# d_pubsub_lower_isolate_220V_common.net
KiCad netlist of a schematic drawn in EAGLE
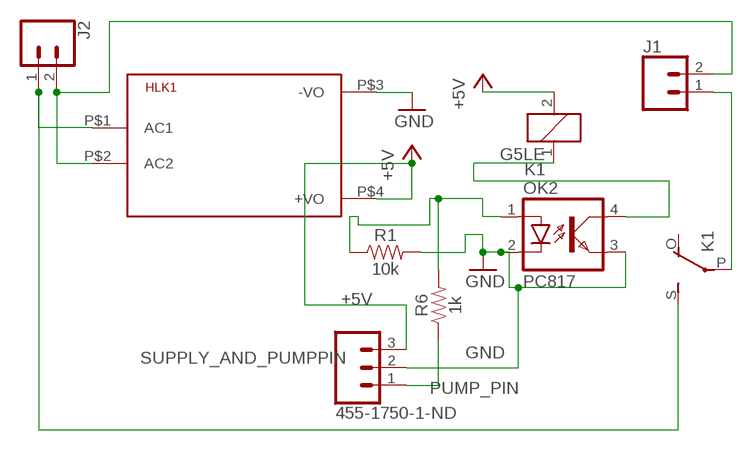
[diagram p0: schematic, sheet 1]

(export (version "E")
  (design (tool "Eeschema 10.0.6"))
  (components
    (comp (ref "HLK1")
      (value "HLK-PM013W")
      (footprint "eagle-import:HLK-PM01")
      (libsource (lib "eagle-import") (part "HLK-PM013W"))
    )
    (comp (ref "J1")
      (value "CONN_025MM")
      (footprint "eagle-import:SCREWTERMINAL-5MM-2")
      (libsource (lib "eagle-import") (part "CONN_025MM"))
    )
    (comp (ref "J2")
      (value "CONN_025MM")
      (footprint "eagle-import:SCREWTERMINAL-5MM-2")
      (libsource (lib "eagle-import") (part "CONN_025MM"))
    )
    (comp (ref "K1")
      (value "G5LE")
      (footprint "eagle-import:G5LE")
      (libsource (lib "eagle-import") (part "G5LE"))
    )
    (comp (ref "OK2")
      (value "PC817")
      (footprint "eagle-import:DIL04")
      (fields (field (name "MPN") "PC817X4J000F"))
      (libsource (lib "eagle-import") (part "PC817"))
    )
    (comp (ref "R1")
      (value "10k")
      (footprint "eagle-import:AXIAL-0.3")
      (libsource (lib "eagle-import") (part "10KOHM-HORIZ-1/4W-1%"))
    )
    (comp (ref "R6")
      (value "1k")
      (footprint "eagle-import:AXIAL-0.3")
      (libsource (lib "eagle-import") (part "1KOHM-HORIZ-1/4W-1%"))
    )
    (comp (ref "SUPPLY_AND_PUMPPIN")
      (value "455-1750-1-ND")
      (footprint "eagle-import:1X03")
      (libsource (lib "eagle-import") (part "CONN_03"))
    )
  )
  (nets
    (net (code "1") (name "+5V") (class "Default")
      (node (ref "HLK1") (pin "P$4") (pinfunction "+VO_P$4") (pintype "bidirectional"))
      (node (ref "K1") (pin "2") (pinfunction "2_2") (pintype "passive"))
      (node (ref "SUPPLY_AND_PUMPPIN") (pin "3") (pinfunction "3_3") (pintype "passive"))
    )
    (net (code "2") (name "/PUMP_PIN") (class "Default")
      (node (ref "R6") (pin "P$1") (pinfunction "1_P$1") (pintype "passive"))
      (node (ref "SUPPLY_AND_PUMPPIN") (pin "1") (pinfunction "1_1") (pintype "passive"))
    )
    (net (code "3") (name "GND") (class "Default")
      (node (ref "HLK1") (pin "P$3") (pinfunction "-VO_P$3") (pintype "bidirectional"))
      (node (ref "OK2") (pin "2") (pinfunction "C_2") (pintype "passive"))
      (node (ref "OK2") (pin "3") (pinfunction "EMIT_3") (pintype "passive"))
      (node (ref "R1") (pin "P$2") (pinfunction "2_P$2") (pintype "passive"))
      (node (ref "SUPPLY_AND_PUMPPIN") (pin "2") (pinfunction "2_2") (pintype "passive"))
    )
    (net (code "4") (name "Net-(HLK1-AC1)") (class "Default")
      (node (ref "HLK1") (pin "P$1") (pinfunction "AC1_P$1") (pintype "bidirectional"))
      (node (ref "J2") (pin "1") (pinfunction "1_1") (pintype "passive"))
      (node (ref "K1") (pin "S") (pinfunction "S_S") (pintype "passive"))
    )
    (net (code "5") (name "Net-(HLK1-AC2)") (class "Default")
      (node (ref "HLK1") (pin "P$2") (pinfunction "AC2_P$2") (pintype "bidirectional"))
      (node (ref "J1") (pin "2") (pinfunction "2_2") (pintype "passive"))
      (node (ref "J2") (pin "2") (pinfunction "2_2") (pintype "passive"))
    )
    (net (code "6") (name "Net-(J1-Pad1)") (class "Default")
      (node (ref "J1") (pin "1") (pinfunction "1_1") (pintype "passive"))
      (node (ref "K1") (pin "P") (pinfunction "P_P") (pintype "passive"))
    )
    (net (code "7") (name "Net-(OK2-A)") (class "Default")
      (node (ref "OK2") (pin "1") (pinfunction "A_1") (pintype "passive"))
      (node (ref "R1") (pin "P$1") (pinfunction "1_P$1") (pintype "passive"))
      (node (ref "R6") (pin "P$2") (pinfunction "2_P$2") (pintype "passive"))
    )
    (net (code "8") (name "Net-(OK2-COL)") (class "Default")
      (node (ref "K1") (pin "1") (pinfunction "1_1") (pintype "passive"))
      (node (ref "OK2") (pin "4") (pinfunction "COL_4") (pintype "passive"))
    )
    (net (code "9") (name "unconnected-(K1-PadO)") (class "Default")
      (node (ref "K1") (pin "O") (pinfunction "O_O") (pintype "passive"))
    )
  )
)
